# POWER.net
KiCad netlist of a schematic drawn in Altium Designer
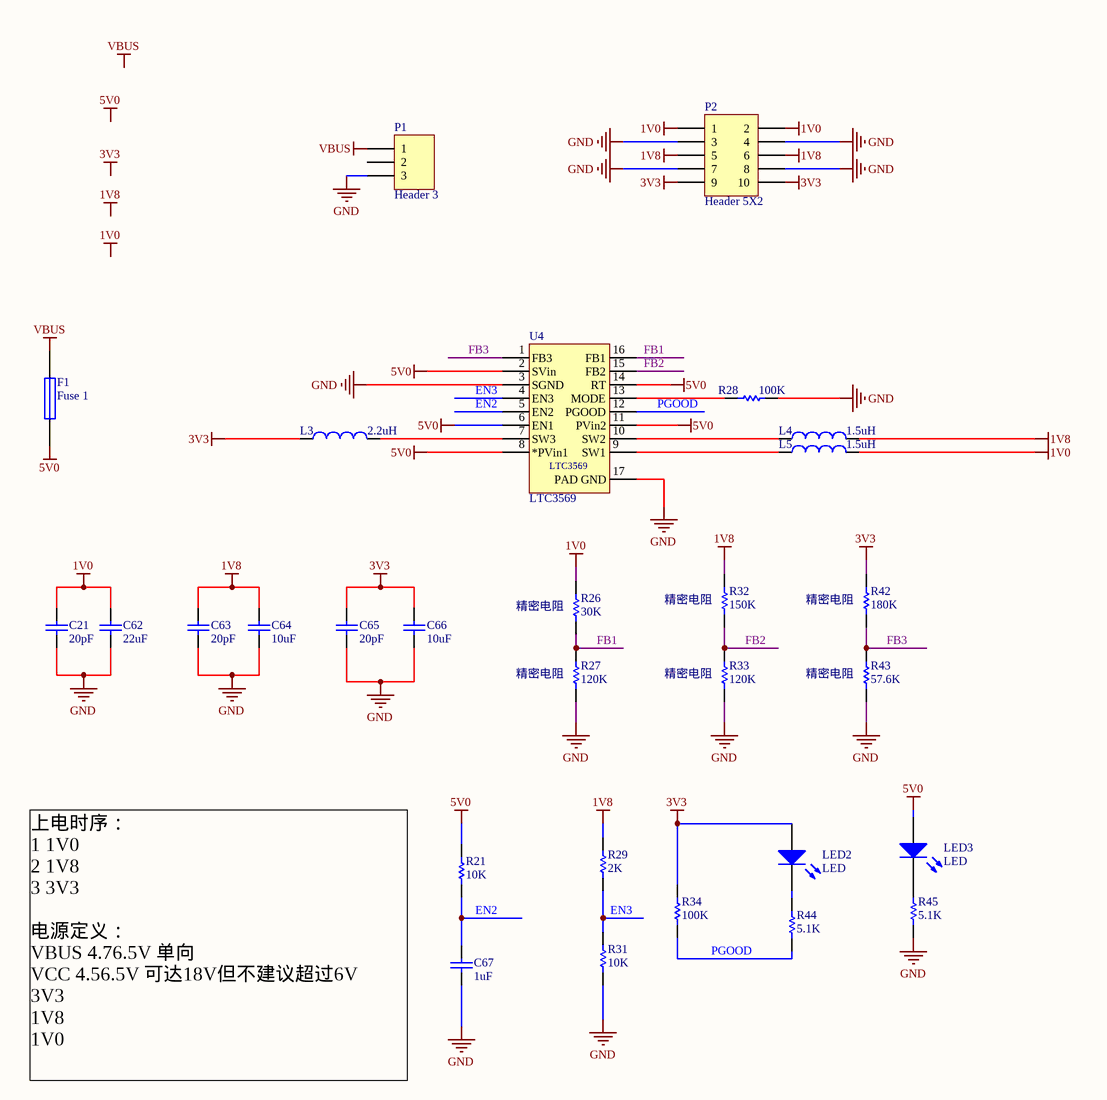
[diagram p0: POWER.SchDoc]

(export (version "E")
  (design (tool "Eeschema 10.0.6"))
  (components
    (comp (ref "C21")
      (value "20pF")
      (footprint "1608[0603]")
      (description "贴片电容")
      (fields (field (name "Comment") "Cap") (field (name "PUBLISHER") "Altium Limited"))
      (libsource (lib "Sparks") (part "Cap"))
    )
    (comp (ref "C62")
      (value "22uF")
      (footprint "1608[0603]")
      (description "贴片电容")
      (fields (field (name "Comment") "Cap") (field (name "PUBLISHER") "Altium Limited"))
      (libsource (lib "Sparks") (part "Cap"))
    )
    (comp (ref "C63")
      (value "20pF")
      (footprint "1608[0603]")
      (description "贴片电容")
      (fields (field (name "Comment") "Cap") (field (name "PUBLISHER") "Altium Limited"))
      (libsource (lib "Sparks") (part "Cap"))
    )
    (comp (ref "C64")
      (value "10uF")
      (footprint "1608[0603]")
      (description "贴片电容")
      (fields (field (name "Comment") "Cap") (field (name "PUBLISHER") "Altium Limited"))
      (libsource (lib "Sparks") (part "Cap"))
    )
    (comp (ref "C65")
      (value "20pF")
      (footprint "1608[0603]")
      (description "贴片电容")
      (fields (field (name "Comment") "Cap") (field (name "PUBLISHER") "Altium Limited"))
      (libsource (lib "Sparks") (part "Cap"))
    )
    (comp (ref "C66")
      (value "10uF")
      (footprint "1608[0603]")
      (description "贴片电容")
      (fields (field (name "Comment") "Cap") (field (name "PUBLISHER") "Altium Limited"))
      (libsource (lib "Sparks") (part "Cap"))
    )
    (comp (ref "C67")
      (value "1uF")
      (footprint "1608[0603]")
      (description "贴片电容")
      (fields (field (name "Comment") "Cap") (field (name "PUBLISHER") "Altium Limited"))
      (libsource (lib "Sparks") (part "Cap"))
    )
    (comp (ref "F1")
      (value "Fuse 1")
      (footprint "1206")
      (description "Fuse")
      (fields (field (name "PUBLISHER") "Altium Limited"))
      (libsource (lib "Miscellaneous Devices") (part "Fuse 1"))
    )
    (comp (ref "L3")
      (value "2.2uH")
      (footprint "C2012")
      (description "Inductor")
      (fields (field (name "PUBLISHER") "Altium Limited"))
      (libsource (lib "Miscellaneous Devices") (part "Inductor"))
    )
    (comp (ref "L4")
      (value "1.5uH")
      (footprint "C2012")
      (description "Inductor")
      (fields (field (name "PUBLISHER") "Altium Limited"))
      (libsource (lib "Miscellaneous Devices") (part "Inductor"))
    )
    (comp (ref "L5")
      (value "1.5uH")
      (footprint "C2012")
      (description "Inductor")
      (fields (field (name "PUBLISHER") "Altium Limited"))
      (libsource (lib "Miscellaneous Devices") (part "Inductor"))
    )
    (comp (ref "LED2") (value "LED") (footprint "1608[0603]") (libsource (lib "Sparks") (part "LED")))
    (comp (ref "LED3") (value "LED") (footprint "1608[0603]") (libsource (lib "Sparks") (part "LED")))
    (comp (ref "P1")
      (value "Header 3")
      (footprint "HDR1X3")
      (description "Header, 3-Pin")
      (fields (field (name "PUBLISHER") "Altium Limited"))
      (libsource (lib "Sparks") (part "Header 3"))
    )
    (comp (ref "P2")
      (value "Header 5X2")
      (footprint "HDR2X5")
      (description "Header, 5-Pin, Dual row")
      (fields (field (name "PUBLISHER") "Altium Limited"))
      (libsource (lib "Sparks") (part "Header 5X2"))
    )
    (comp (ref "R21")
      (value "10K")
      (footprint "1608[0603]")
      (description "贴片电阻")
      (fields (field (name "PUBLISHER") "Altium Limited"))
      (libsource (lib "Sparks") (part "Res"))
    )
    (comp (ref "R26")
      (value "精密电阻")
      (footprint "1608[0603]")
      (description "贴片电阻")
      (fields (field (name "ALTIUM_VALUE") "30K") (field (name "PUBLISHER") "Altium Limited"))
      (libsource (lib "Sparks") (part "Res"))
    )
    (comp (ref "R27")
      (value "精密电阻")
      (footprint "1608[0603]")
      (description "贴片电阻")
      (fields (field (name "ALTIUM_VALUE") "120K") (field (name "PUBLISHER") "Altium Limited"))
      (libsource (lib "Sparks") (part "Res"))
    )
    (comp (ref "R28")
      (value "100K")
      (footprint "1608[0603]")
      (description "贴片电阻")
      (fields (field (name "PUBLISHER") "Altium Limited"))
      (libsource (lib "Sparks") (part "Res"))
    )
    (comp (ref "R29")
      (value "2K")
      (footprint "1608[0603]")
      (description "贴片电阻")
      (fields (field (name "PUBLISHER") "Altium Limited"))
      (libsource (lib "Sparks") (part "Res"))
    )
    (comp (ref "R31")
      (value "10K")
      (footprint "1608[0603]")
      (description "贴片电阻")
      (fields (field (name "PUBLISHER") "Altium Limited"))
      (libsource (lib "Sparks") (part "Res"))
    )
    (comp (ref "R32")
      (value "精密电阻")
      (footprint "1608[0603]")
      (description "贴片电阻")
      (fields (field (name "ALTIUM_VALUE") "150K") (field (name "PUBLISHER") "Altium Limited"))
      (libsource (lib "Sparks") (part "Res"))
    )
    (comp (ref "R33")
      (value "精密电阻")
      (footprint "1608[0603]")
      (description "贴片电阻")
      (fields (field (name "ALTIUM_VALUE") "120K") (field (name "PUBLISHER") "Altium Limited"))
      (libsource (lib "Sparks") (part "Res"))
    )
    (comp (ref "R34")
      (value "100K")
      (footprint "1608[0603]")
      (description "贴片电阻")
      (fields (field (name "PUBLISHER") "Altium Limited"))
      (libsource (lib "Sparks") (part "Res"))
    )
    (comp (ref "R42")
      (value "精密电阻")
      (footprint "1608[0603]")
      (description "贴片电阻")
      (fields (field (name "ALTIUM_VALUE") "180K") (field (name "PUBLISHER") "Altium Limited"))
      (libsource (lib "Sparks") (part "Res"))
    )
    (comp (ref "R43")
      (value "精密电阻")
      (footprint "1608[0603]")
      (description "贴片电阻")
      (fields (field (name "ALTIUM_VALUE") "57.6K") (field (name "PUBLISHER") "Altium Limited"))
      (libsource (lib "Sparks") (part "Res"))
    )
    (comp (ref "R44")
      (value "5.1K")
      (footprint "1608[0603]")
      (description "贴片电阻")
      (fields (field (name "PUBLISHER") "Altium Limited"))
      (libsource (lib "Sparks") (part "Res"))
    )
    (comp (ref "R45")
      (value "5.1K")
      (footprint "1608[0603]")
      (description "贴片电阻")
      (fields (field (name "PUBLISHER") "Altium Limited"))
      (libsource (lib "Sparks") (part "Res"))
    )
    (comp (ref "U4")
      (value "LTC3569")
      (footprint "SOP127P600-8N")
      (libsource (lib "Schlib") (part "LTC3569"))
    )
  )
  (nets
    (net (code "1") (name "/EN2") (class "Default")
      (node (ref "C67") (pin "1") (pinfunction "1_1") (pintype "passive"))
      (node (ref "R21") (pin "2") (pinfunction "2_2") (pintype "passive"))
      (node (ref "U4") (pin "5") (pinfunction "EN2_5") (pintype "passive"))
    )
    (net (code "2") (name "/EN3") (class "Default")
      (node (ref "R29") (pin "2") (pinfunction "2_2") (pintype "passive"))
      (node (ref "R31") (pin "1") (pinfunction "1_1") (pintype "passive"))
      (node (ref "U4") (pin "4") (pinfunction "EN3_4") (pintype "passive"))
    )
    (net (code "3") (name "/FB1") (class "Default")
      (node (ref "R26") (pin "2") (pinfunction "2_2") (pintype "passive"))
      (node (ref "R27") (pin "1") (pinfunction "1_1") (pintype "passive"))
      (node (ref "U4") (pin "16") (pinfunction "FB1_16") (pintype "passive"))
    )
    (net (code "4") (name "/FB2") (class "Default")
      (node (ref "R32") (pin "2") (pinfunction "2_2") (pintype "passive"))
      (node (ref "R33") (pin "1") (pinfunction "1_1") (pintype "passive"))
      (node (ref "U4") (pin "15") (pinfunction "FB2_15") (pintype "passive"))
    )
    (net (code "5") (name "/FB3") (class "Default")
      (node (ref "R42") (pin "2") (pinfunction "2_2") (pintype "passive"))
      (node (ref "R43") (pin "1") (pinfunction "1_1") (pintype "passive"))
      (node (ref "U4") (pin "1") (pinfunction "FB3_1") (pintype "passive"))
    )
    (net (code "6") (name "/PGOOD") (class "Default")
      (node (ref "R34") (pin "2") (pinfunction "2_2") (pintype "passive"))
      (node (ref "R44") (pin "2") (pinfunction "2_2") (pintype "passive"))
      (node (ref "U4") (pin "12") (pinfunction "PGOOD_12") (pintype "passive"))
    )
    (net (code "7") (name "1V0") (class "Default")
      (node (ref "C21") (pin "1") (pinfunction "1_1") (pintype "passive"))
      (node (ref "C62") (pin "1") (pinfunction "1_1") (pintype "passive"))
      (node (ref "L5") (pin "2") (pinfunction "2_2") (pintype "passive"))
      (node (ref "P2") (pin "1") (pinfunction "1_1") (pintype "passive"))
      (node (ref "P2") (pin "2") (pinfunction "2_2") (pintype "passive"))
      (node (ref "R26") (pin "1") (pinfunction "1_1") (pintype "passive"))
    )
    (net (code "8") (name "1V8") (class "Default")
      (node (ref "C63") (pin "1") (pinfunction "1_1") (pintype "passive"))
      (node (ref "C64") (pin "1") (pinfunction "1_1") (pintype "passive"))
      (node (ref "L4") (pin "2") (pinfunction "2_2") (pintype "passive"))
      (node (ref "P2") (pin "5") (pinfunction "5_5") (pintype "passive"))
      (node (ref "P2") (pin "6") (pinfunction "6_6") (pintype "passive"))
      (node (ref "R29") (pin "1") (pinfunction "1_1") (pintype "passive"))
      (node (ref "R32") (pin "1") (pinfunction "1_1") (pintype "passive"))
    )
    (net (code "9") (name "3V3") (class "Default")
      (node (ref "C65") (pin "1") (pinfunction "1_1") (pintype "passive"))
      (node (ref "C66") (pin "1") (pinfunction "1_1") (pintype "passive"))
      (node (ref "L3") (pin "1") (pinfunction "1_1") (pintype "passive"))
      (node (ref "LED2") (pin "1") (pinfunction "A_1") (pintype "passive"))
      (node (ref "P2") (pin "10") (pinfunction "10_10") (pintype "passive"))
      (node (ref "P2") (pin "9") (pinfunction "9_9") (pintype "passive"))
      (node (ref "R34") (pin "1") (pinfunction "1_1") (pintype "passive"))
      (node (ref "R42") (pin "1") (pinfunction "1_1") (pintype "passive"))
    )
    (net (code "10") (name "5V0") (class "Default")
      (node (ref "F1") (pin "1") (pinfunction "1_1") (pintype "passive"))
      (node (ref "LED3") (pin "1") (pinfunction "A_1") (pintype "passive"))
      (node (ref "R21") (pin "1") (pinfunction "1_1") (pintype "passive"))
      (node (ref "U4") (pin "11") (pinfunction "PVin2_11") (pintype "passive"))
      (node (ref "U4") (pin "14") (pinfunction "RT_14") (pintype "passive"))
      (node (ref "U4") (pin "2") (pinfunction "SVin_2") (pintype "passive"))
      (node (ref "U4") (pin "6") (pinfunction "EN1_6") (pintype "passive"))
      (node (ref "U4") (pin "8") (pinfunction "*PVin1_8") (pintype "passive"))
    )
    (net (code "11") (name "GND") (class "Default")
      (node (ref "C21") (pin "2") (pinfunction "2_2") (pintype "passive"))
      (node (ref "C62") (pin "2") (pinfunction "2_2") (pintype "passive"))
      (node (ref "C63") (pin "2") (pinfunction "2_2") (pintype "passive"))
      (node (ref "C64") (pin "2") (pinfunction "2_2") (pintype "passive"))
      (node (ref "C65") (pin "2") (pinfunction "2_2") (pintype "passive"))
      (node (ref "C66") (pin "2") (pinfunction "2_2") (pintype "passive"))
      (node (ref "C67") (pin "2") (pinfunction "2_2") (pintype "passive"))
      (node (ref "P1") (pin "3") (pinfunction "3_3") (pintype "passive"))
      (node (ref "P2") (pin "3") (pinfunction "3_3") (pintype "passive"))
      (node (ref "P2") (pin "4") (pinfunction "4_4") (pintype "passive"))
      (node (ref "P2") (pin "7") (pinfunction "7_7") (pintype "passive"))
      (node (ref "P2") (pin "8") (pinfunction "8_8") (pintype "passive"))
      (node (ref "R27") (pin "2") (pinfunction "2_2") (pintype "passive"))
      (node (ref "R28") (pin "1") (pinfunction "1_1") (pintype "passive"))
      (node (ref "R31") (pin "2") (pinfunction "2_2") (pintype "passive"))
      (node (ref "R33") (pin "2") (pinfunction "2_2") (pintype "passive"))
      (node (ref "R43") (pin "2") (pinfunction "2_2") (pintype "passive"))
      (node (ref "R45") (pin "2") (pinfunction "2_2") (pintype "passive"))
      (node (ref "U4") (pin "17") (pinfunction "PAD_GND_17") (pintype "passive"))
      (node (ref "U4") (pin "3") (pinfunction "SGND_3") (pintype "passive"))
    )
    (net (code "12") (name "Net-(LED2-K)") (class "Default")
      (node (ref "LED2") (pin "2") (pinfunction "K_2") (pintype "passive"))
      (node (ref "R44") (pin "1") (pinfunction "1_1") (pintype "passive"))
    )
    (net (code "13") (name "Net-(LED3-K)") (class "Default")
      (node (ref "LED3") (pin "2") (pinfunction "K_2") (pintype "passive"))
      (node (ref "R45") (pin "1") (pinfunction "1_1") (pintype "passive"))
    )
    (net (code "14") (name "Net-(U4-MODE)") (class "Default")
      (node (ref "R28") (pin "2") (pinfunction "2_2") (pintype "passive"))
      (node (ref "U4") (pin "13") (pinfunction "MODE_13") (pintype "passive"))
    )
    (net (code "15") (name "Net-(U4-SW1)") (class "Default")
      (node (ref "L5") (pin "1") (pinfunction "1_1") (pintype "passive"))
      (node (ref "U4") (pin "9") (pinfunction "SW1_9") (pintype "passive"))
    )
    (net (code "16") (name "Net-(U4-SW2)") (class "Default")
      (node (ref "L4") (pin "1") (pinfunction "1_1") (pintype "passive"))
      (node (ref "U4") (pin "10") (pinfunction "SW2_10") (pintype "passive"))
    )
    (net (code "17") (name "Net-(U4-SW3)") (class "Default")
      (node (ref "L3") (pin "2") (pinfunction "2_2") (pintype "passive"))
      (node (ref "U4") (pin "7") (pinfunction "SW3_7") (pintype "passive"))
    )
    (net (code "18") (name "VBUS") (class "Default")
      (node (ref "F1") (pin "2") (pinfunction "2_2") (pintype "passive"))
      (node (ref "P1") (pin "1") (pinfunction "1_1") (pintype "passive"))
    )
    (net (code "19") (name "unconnected-(P1-Pad2)") (class "Default")
      (node (ref "P1") (pin "2") (pinfunction "2_2") (pintype "passive"))
    )
  )
)
